# NGI_Search_StepDown_lab.net
KiCad netlist of a schematic drawn in Altium Designer
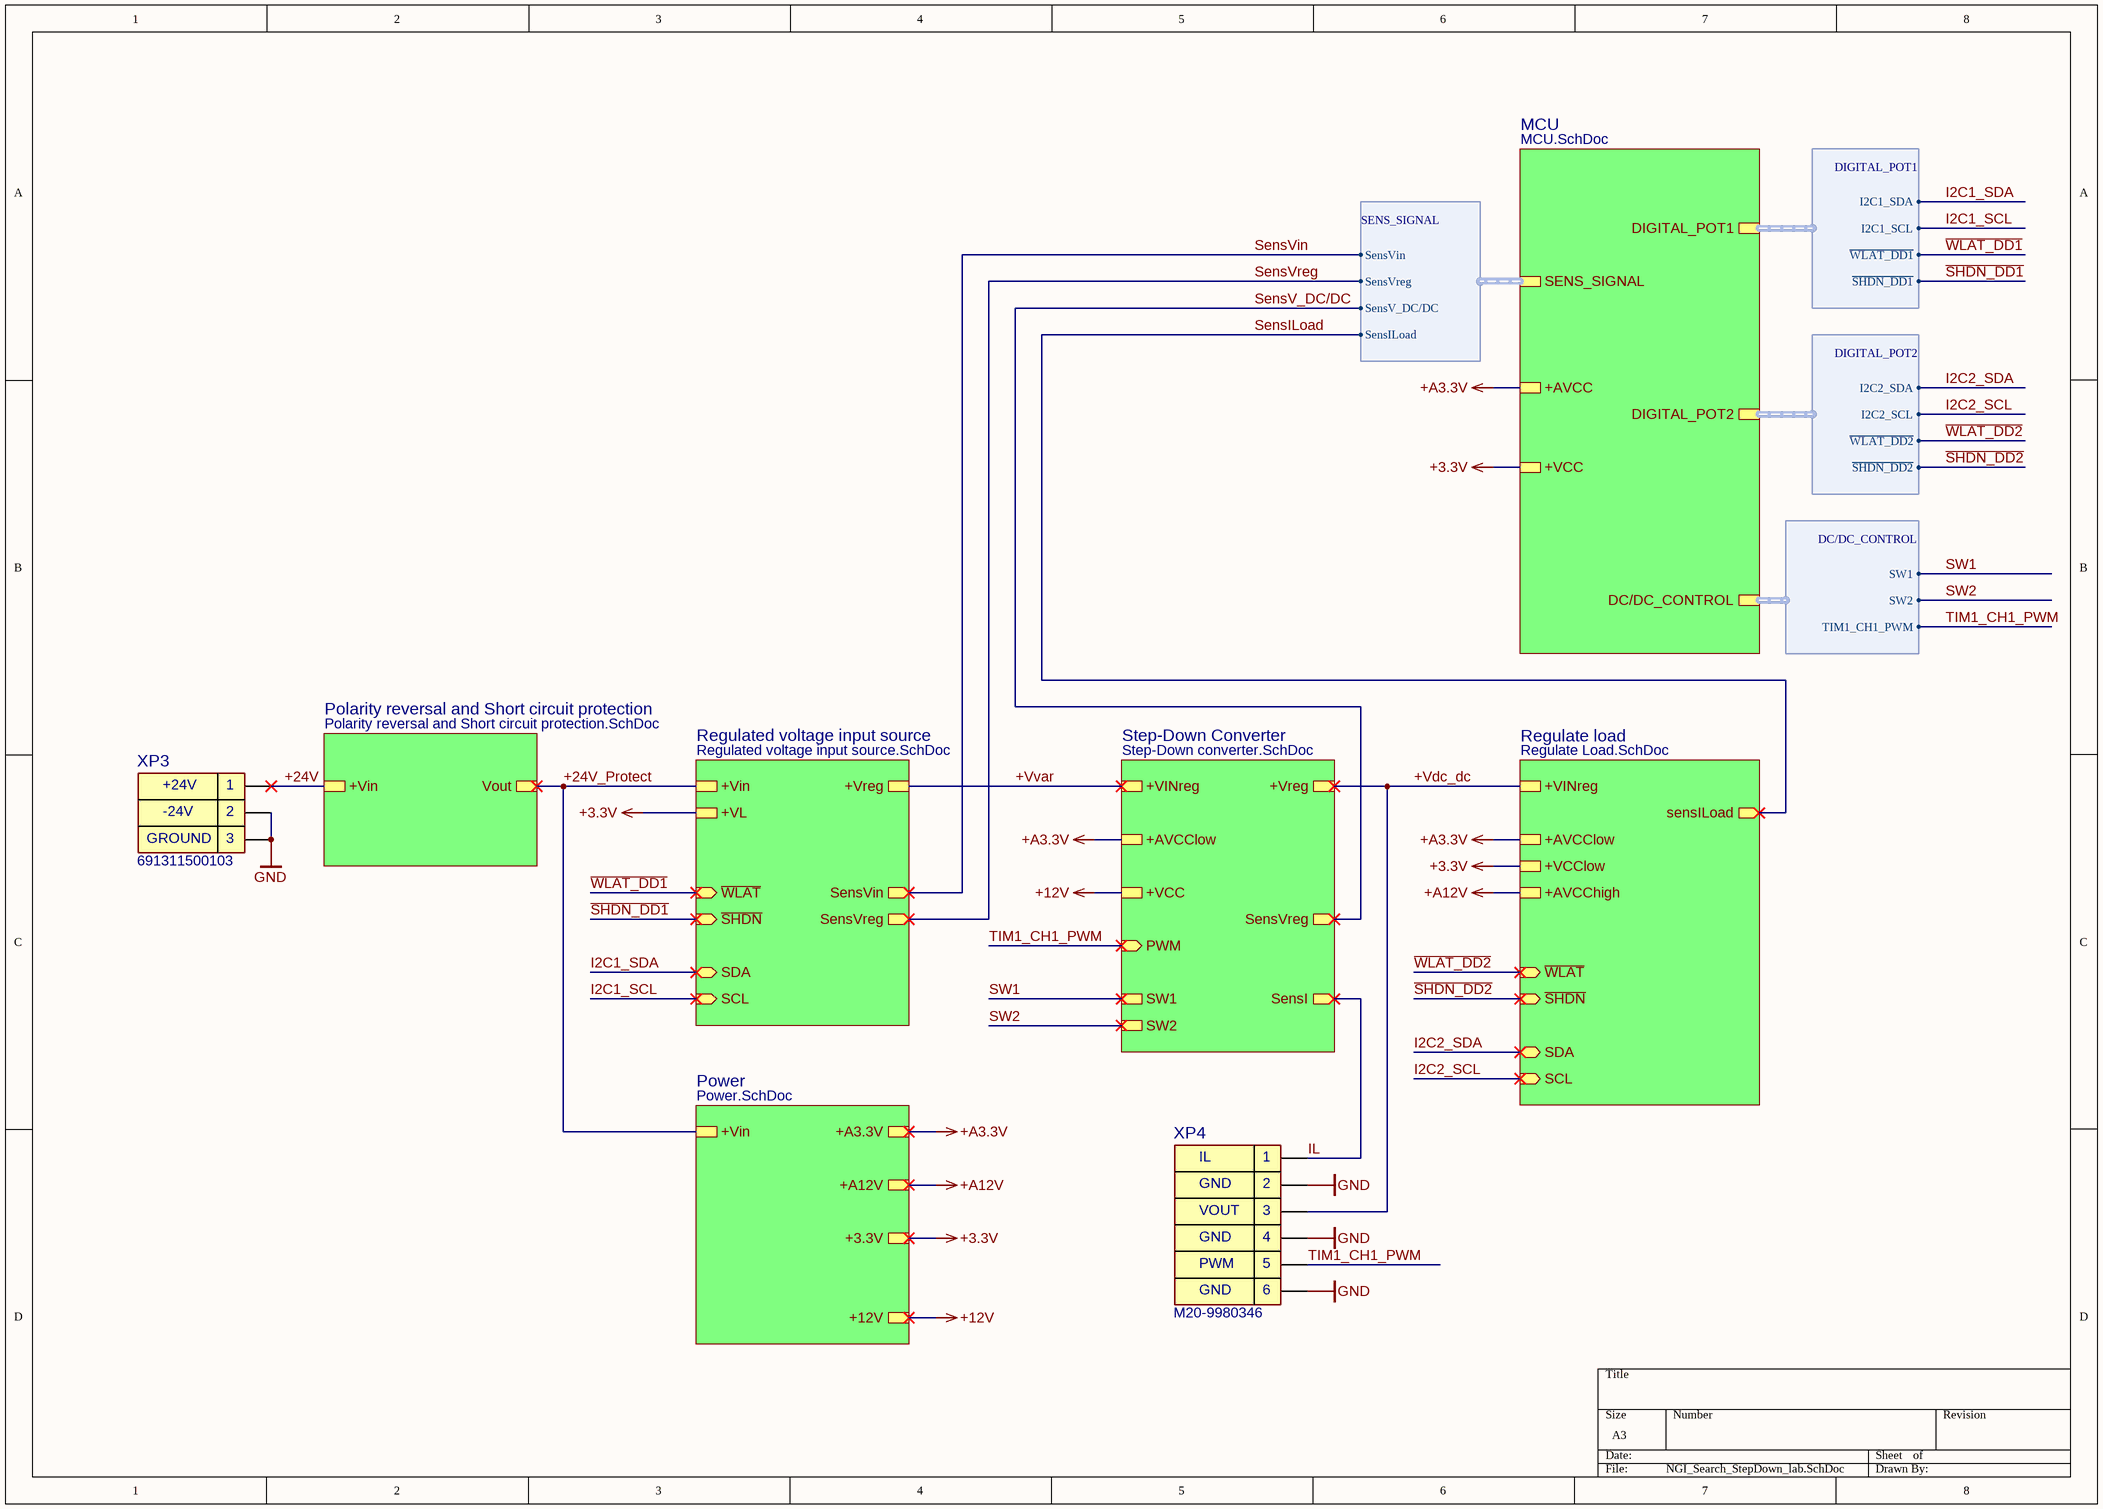
[diagram p0: NGI_Search_StepDown_lab.SchDoc]

(export (version "E")
  (design (tool "Eeschema 10.0.6"))
  (components
    (comp (ref "XP3")
      (value "691311500103")
      (footprint "691311500103")
      (description "Pluggable Terminal Blocks WR-TBL 300VAC 20A 3P Vertical")
      (fields
        (field (name "MANUFACTURER") "Wurth Elektronik")
        (field (name "MOUSER PART NUMBER") "710-691311500103")
      )
      (libsource (lib "NGI_Search") (part "691311500103"))
    )
    (comp (ref "XP4")
      (value "M20-9980346")
      (footprint "M20-9980346")
      (description "Headers & Wire Housings 03+03 DIL VERTICAL PIN HEADER TIN")
      (fields (field (name "MANUFACTURER") "Harwin") (field (name "MOUSER PART NUMBER") "855-M20-9980346"))
      (libsource (lib "NGI_Search") (part "M20-9980346"))
    )
  )
  (nets
    (net (code "9") (name "/+24V") (class "Default")
      (node (ref "XP3") (pin "1") (pintype "passive+no_connect"))
    )
    (net (code "11") (name "/+Vdc_dc") (class "Default")
      (node (ref "XP4") (pin "3") (pintype "passive+no_connect"))
    )
    (net (code "17") (name "/IL") (class "Default")
      (node (ref "XP4") (pin "1") (pintype "passive+no_connect"))
    )
    (net (code "24") (name "/TIM1_CH1_PWM") (class "Default")
      (node (ref "XP4") (pin "5") (pintype "passive"))
    )
    (net (code "33") (name "GND") (class "Default")
      (node (ref "XP3") (pin "2") (pintype "passive"))
      (node (ref "XP3") (pin "3") (pintype "passive"))
      (node (ref "XP4") (pin "2") (pintype "passive"))
      (node (ref "XP4") (pin "4") (pintype "passive"))
      (node (ref "XP4") (pin "6") (pintype "passive"))
    )
  )
)
